# cpuotg.net
KiCad netlist of a schematic drawn in Altium Designer
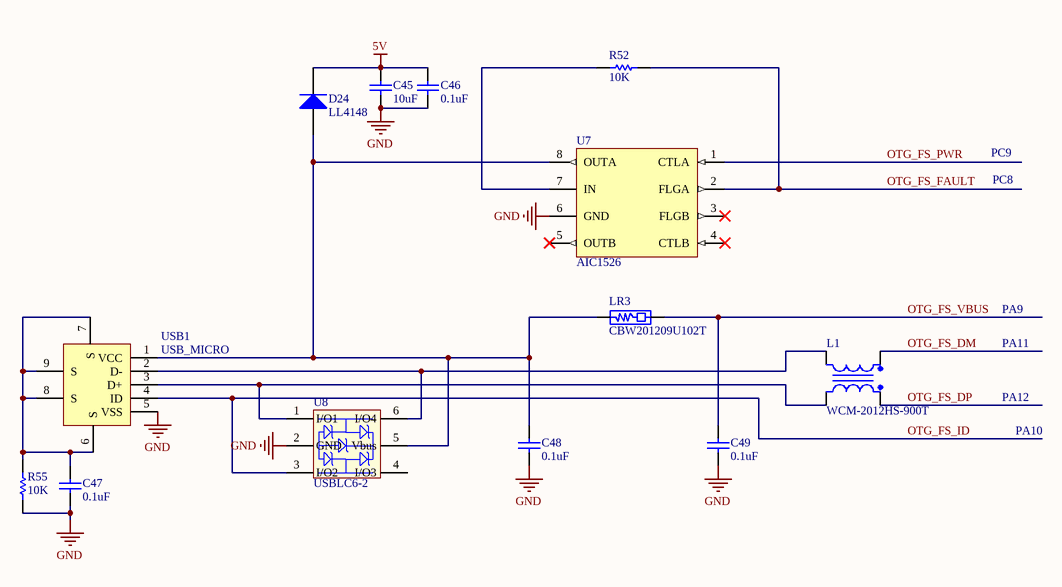
[diagram p0: cpuotg.SchDoc]

(export (version "E")
  (design (tool "Eeschema 10.0.6"))
  (components
    (comp (ref "C45")
      (value "10uF")
      (footprint "CAPC2012M")
      (description "Capacitor")
      (fields (field (name "PUBLISHER") "Altium Limited"))
      (libsource (lib "Miscellaneous Devices") (part "Cap"))
    )
    (comp (ref "C46")
      (value "0.1uF")
      (footprint "CAPC2012M")
      (description "Capacitor")
      (fields (field (name "PUBLISHER") "Altium Limited"))
      (libsource (lib "Miscellaneous Devices") (part "Cap"))
    )
    (comp (ref "C47")
      (value "0.1uF")
      (footprint "CAPC2012M")
      (description "Capacitor")
      (fields (field (name "PUBLISHER") "Altium Limited"))
      (libsource (lib "Miscellaneous Devices") (part "Cap"))
    )
    (comp (ref "C48")
      (value "0.1uF")
      (footprint "CAPC2012M")
      (description "Capacitor")
      (fields (field (name "PUBLISHER") "Altium Limited"))
      (libsource (lib "Miscellaneous Devices") (part "Cap"))
    )
    (comp (ref "C49")
      (value "0.1uF")
      (footprint "CAPC2012M")
      (description "Capacitor")
      (fields (field (name "PUBLISHER") "Altium Limited"))
      (libsource (lib "Miscellaneous Devices") (part "Cap"))
    )
    (comp (ref "D24")
      (value "LL4148")
      (footprint "CD3216-1206")
      (description "1 Amp General Purpose Rectifier")
      (fields (field (name "PUBLISHER") "Altium Limited"))
      (libsource (lib "Miscellaneous Devices") (part "Diode 1N4007"))
    )
    (comp (ref "L1")
      (value "WCM-2012HS-900T")
      (footprint "WCM-2012HS-900T")
      (description "Conjugate stream coil,pitch 7.62mmx8mm(LxW)")
      (fields (field (name "PUBLISHER") "Altium Limited"))
      (libsource (lib "UserLib") (part "Inductor Iron Dot Inphase"))
    )
    (comp (ref "LR3")
      (value "CBW201209U102T")
      (footprint "INDC2012M")
      (description "EMI FILTERS,DC Resistance max.0.05~1.5 ohms,10 ~ 1000 ohms at 100MHz  Frequency")
      (libsource (lib "UserLib") (part "BLM10/11/21/31/41"))
    )
    (comp (ref "R52")
      (value "10K")
      (footprint "RESC2012M")
      (description "Resistor")
      (fields (field (name "PUBLISHER") "Altium Limited"))
      (libsource (lib "Miscellaneous Devices") (part "Res1"))
    )
    (comp (ref "R55")
      (value "10K")
      (footprint "RESC2012M")
      (description "Resistor")
      (fields (field (name "PUBLISHER") "Altium Limited"))
      (libsource (lib "Miscellaneous Devices") (part "Res1"))
    )
    (comp (ref "U7")
      (value "AIC1526")
      (footprint "SOP-8")
      (description "Dual USB High-Side Power Switch")
      (libsource (lib "UserSchDev") (part "AIC1526"))
    )
    (comp (ref "U8")
      (value "USBLC6-2")
      (footprint "SOT23-6_L")
      (description "USB ESD Protection Diode Array,±15kV (air), ±8kV (contact),Working Voltages 5V")
      (libsource (lib "UserSchDev") (part "USBLC6-2"))
    )
    (comp (ref "USB1")
      (value "USB_MICRO")
      (footprint "USB-MICRO-B")
      (description "MicroUSB接口")
      (libsource (lib "UserSchDev") (part "USB_MICRO"))
    )
  )
  (nets
    (net (code "1") (name "/OTG_FS_DM") (class "Default")
      (node (ref "L1") (pin "2") (pinfunction "Sec+_2") (pintype "passive"))
    )
    (net (code "2") (name "/OTG_FS_DP") (class "Default")
      (node (ref "L1") (pin "1") (pinfunction "Pri+_1") (pintype "passive"))
    )
    (net (code "3") (name "/OTG_FS_FAULT") (class "Default")
      (node (ref "R52") (pin "2") (pinfunction "2_2") (pintype "passive"))
      (node (ref "U7") (pin "2") (pinfunction "FLGA_2") (pintype "output"))
    )
    (net (code "4") (name "/OTG_FS_ID") (class "Default")
      (node (ref "U8") (pin "3") (pinfunction "I/O2_3") (pintype "passive"))
      (node (ref "USB1") (pin "4") (pinfunction "ID_4") (pintype "passive"))
    )
    (net (code "5") (name "/OTG_FS_PWR") (class "Default")
      (node (ref "U7") (pin "1") (pinfunction "CTLA_1") (pintype "input"))
    )
    (net (code "6") (name "/OTG_FS_VBUS") (class "Default")
      (node (ref "C49") (pin "1") (pinfunction "1_1") (pintype "passive"))
      (node (ref "LR3") (pin "2") (pinfunction "2_2") (pintype "passive"))
    )
    (net (code "7") (name "5V") (class "Default")
      (node (ref "C45") (pin "1") (pinfunction "1_1") (pintype "passive"))
      (node (ref "C46") (pin "1") (pinfunction "1_1") (pintype "passive"))
      (node (ref "D24") (pin "2") (pinfunction "K_2") (pintype "passive"))
    )
    (net (code "8") (name "GND") (class "Default")
      (node (ref "C45") (pin "2") (pinfunction "2_2") (pintype "passive"))
      (node (ref "C46") (pin "2") (pinfunction "2_2") (pintype "passive"))
      (node (ref "C47") (pin "2") (pinfunction "2_2") (pintype "passive"))
      (node (ref "C48") (pin "2") (pinfunction "2_2") (pintype "passive"))
      (node (ref "C49") (pin "2") (pinfunction "2_2") (pintype "passive"))
      (node (ref "R55") (pin "1") (pinfunction "1_1") (pintype "passive"))
      (node (ref "U7") (pin "6") (pinfunction "GND_6") (pintype "power_in"))
      (node (ref "U8") (pin "2") (pinfunction "GND_2") (pintype "passive"))
      (node (ref "USB1") (pin "5") (pinfunction "VSS_5") (pintype "passive"))
    )
    (net (code "9") (name "Net-(C47-Pad1)") (class "Default")
      (node (ref "C47") (pin "1") (pinfunction "1_1") (pintype "passive"))
      (node (ref "R55") (pin "2") (pinfunction "2_2") (pintype "passive"))
      (node (ref "USB1") (pin "6") (pinfunction "S_6") (pintype "passive"))
      (node (ref "USB1") (pin "7") (pinfunction "S_7") (pintype "passive"))
      (node (ref "USB1") (pin "8") (pinfunction "S_8") (pintype "passive"))
      (node (ref "USB1") (pin "9") (pinfunction "S_9") (pintype "passive"))
    )
    (net (code "10") (name "Net-(D24-A)") (class "Default")
      (node (ref "C48") (pin "1") (pinfunction "1_1") (pintype "passive"))
      (node (ref "D24") (pin "1") (pinfunction "A_1") (pintype "passive"))
      (node (ref "LR3") (pin "1") (pinfunction "1_1") (pintype "passive"))
      (node (ref "U7") (pin "8") (pinfunction "OUTA_8") (pintype "output"))
      (node (ref "U8") (pin "5") (pinfunction "Vbus_5") (pintype "passive"))
      (node (ref "USB1") (pin "1") (pinfunction "VCC_1") (pintype "passive"))
    )
    (net (code "11") (name "Net-(L1-Pri-)") (class "Default")
      (node (ref "L1") (pin "3") (pinfunction "Pri-_3") (pintype "passive"))
      (node (ref "U8") (pin "1") (pinfunction "I/O1_1") (pintype "passive"))
      (node (ref "USB1") (pin "3") (pinfunction "D+_3") (pintype "passive"))
    )
    (net (code "12") (name "Net-(L1-Sec-)") (class "Default")
      (node (ref "L1") (pin "4") (pinfunction "Sec-_4") (pintype "passive"))
      (node (ref "U8") (pin "6") (pinfunction "I/O4_6") (pintype "passive"))
      (node (ref "USB1") (pin "2") (pinfunction "D-_2") (pintype "passive"))
    )
    (net (code "13") (name "Net-(U7-IN)") (class "Default")
      (node (ref "R52") (pin "1") (pinfunction "1_1") (pintype "passive"))
      (node (ref "U7") (pin "7") (pinfunction "IN_7") (pintype "power_in"))
    )
    (net (code "14") (name "unconnected-(U7-CTLB-Pad4)") (class "Default")
      (node (ref "U7") (pin "4") (pinfunction "CTLB_4") (pintype "input+no_connect"))
    )
    (net (code "15") (name "unconnected-(U7-FLGB-Pad3)") (class "Default")
      (node (ref "U7") (pin "3") (pinfunction "FLGB_3") (pintype "output+no_connect"))
    )
    (net (code "16") (name "unconnected-(U7-OUTB-Pad5)") (class "Default")
      (node (ref "U7") (pin "5") (pinfunction "OUTB_5") (pintype "output+no_connect"))
    )
    (net (code "17") (name "unconnected-(U8-I{slash}O3-Pad4)") (class "Default")
      (node (ref "U8") (pin "4") (pinfunction "I/O3_4") (pintype "passive"))
    )
  )
)
